# IO.net
KiCad netlist of a schematic drawn in Altium Designer
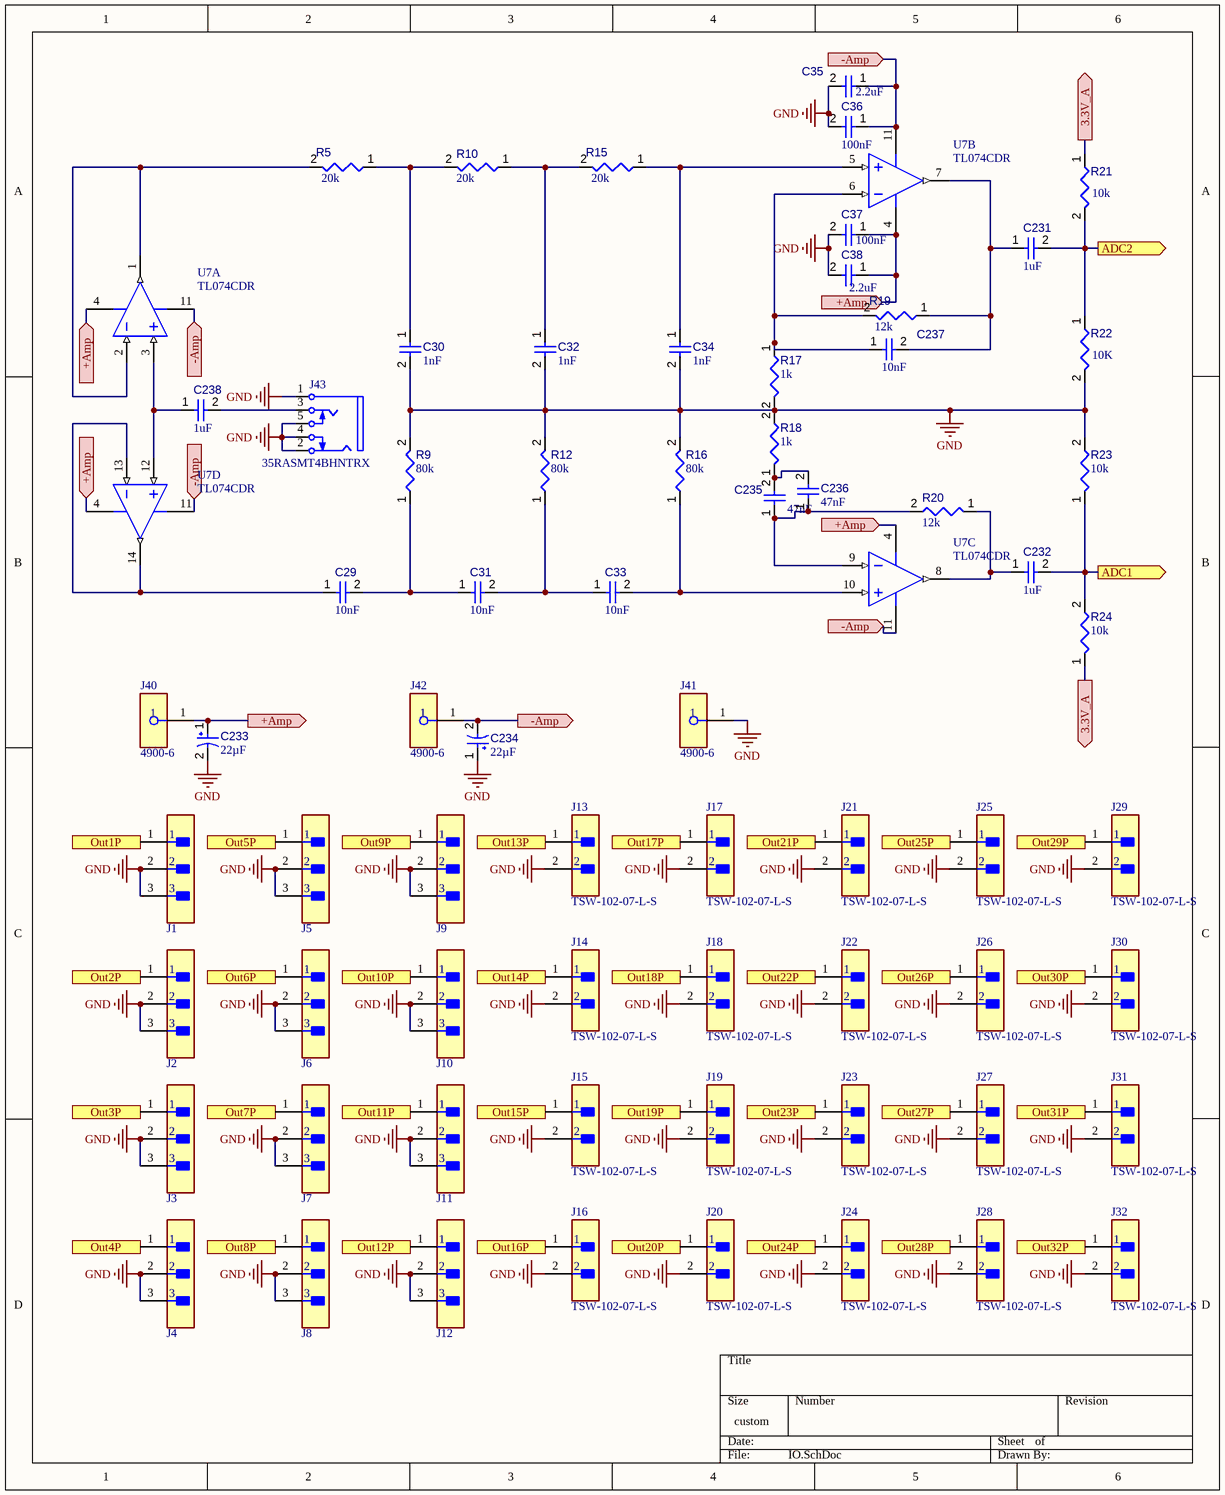
[diagram p0: IO.SchDoc]

(export (version "E")
  (design (tool "Eeschema 10.0.6"))
  (components
    (comp (ref "C29")
      (value "10nF")
      (footprint "CAPC0603(1608)100_L")
      (description "8nF Cap 0603")
      (fields (field (name "TOLERANCE") "10%") (field (name "Comment") "Capacitor 8nF 0603, 12V"))
      (libsource (lib "Northeastern University") (part "CAP-NP-2"))
    )
    (comp (ref "C30")
      (value "1nF")
      (footprint "CAPC0603(1608)100_L")
      (description "1nF 0603")
      (fields (field (name "TOLERANCE") "10%") (field (name "Comment") "Capacitor 1nF 0603, 12V"))
      (libsource (lib "Northeastern University") (part "CAP-NP-2"))
    )
    (comp (ref "C31")
      (value "10nF")
      (footprint "CAPC0603(1608)100_L")
      (description "8nF Cap 0603")
      (fields (field (name "TOLERANCE") "10%") (field (name "Comment") "Capacitor 8nF 0603, 12V"))
      (libsource (lib "Northeastern University") (part "CAP-NP-2"))
    )
    (comp (ref "C32")
      (value "1nF")
      (footprint "CAPC0603(1608)100_L")
      (description "1nF 0603")
      (fields (field (name "TOLERANCE") "10%") (field (name "Comment") "Capacitor 1nF 0603, 12V"))
      (libsource (lib "Northeastern University") (part "CAP-NP-2"))
    )
    (comp (ref "C33")
      (value "10nF")
      (footprint "CAPC0603(1608)100_L")
      (description "8nF Cap 0603")
      (fields (field (name "TOLERANCE") "10%") (field (name "Comment") "Capacitor 10nF 0603, 12V"))
      (libsource (lib "Northeastern University") (part "CAP-NP-2"))
    )
    (comp (ref "C34")
      (value "1nF")
      (footprint "CAPC0603(1608)100_L")
      (description "1nF 0603")
      (fields (field (name "TOLERANCE") "10%") (field (name "Comment") "Capacitor 1nF 0603, 12V"))
      (libsource (lib "Northeastern University") (part "CAP-NP-2"))
    )
    (comp (ref "C35")
      (value "2.2uF")
      (footprint "CAPC0603(1608)100_L")
      (fields (field (name "TOLERANCE") "10%") (field (name "Comment") "Capacitor 2.2uF 0603"))
      (libsource (lib "Northeastern University") (part "CAP-NP-2"))
    )
    (comp (ref "C36")
      (value "100nF")
      (footprint "CAPC0603(1608)100_L")
      (fields (field (name "TOLERANCE") "10%") (field (name "Comment") "Capacitor 100nF 0603"))
      (libsource (lib "Northeastern University") (part "CAP-NP-2"))
    )
    (comp (ref "C37")
      (value "100nF")
      (footprint "CAPC0603(1608)100_L")
      (fields (field (name "TOLERANCE") "10%") (field (name "Comment") "Capacitor 100nF 0603"))
      (libsource (lib "Northeastern University") (part "CAP-NP-2"))
    )
    (comp (ref "C38")
      (value "2.2uF")
      (footprint "CAPC0603(1608)100_L")
      (fields (field (name "TOLERANCE") "10%") (field (name "Comment") "Capacitor 2.2uF 0603"))
      (libsource (lib "Northeastern University") (part "CAP-NP-2"))
    )
    (comp (ref "C231")
      (value "1uF")
      (footprint "CAPC0603(1608)100_L")
      (description "1uF 0603")
      (fields (field (name "TOLERANCE") "10%") (field (name "Comment") "Capacitor 1uF 0603, 12V"))
      (libsource (lib "Northeastern University") (part "CAP-NP-2"))
    )
    (comp (ref "C232")
      (value "1uF")
      (footprint "CAPC0603(1608)100_L")
      (description "1uF 0603")
      (fields (field (name "TOLERANCE") "10%") (field (name "Comment") "Capacitor 1uF 0603, 12V"))
      (libsource (lib "Northeastern University") (part "CAP-NP-2"))
    )
    (comp (ref "C233")
      (value "22µF")
      (footprint "CAPPR55-250-1120X630X1220")
      (description "Aluminum Electrolytic Capacitor, 22 uF, +/- 20%, 100 V, -40 to 85 degC, 2-Pin THD, RoHS, Bulk")
      (fields (field (name "MANUFACTURER") "Panasonic") (field (name "TOLERANCE") "20%"))
      (libsource (lib "Northeastern University") (part "CAP-P-2"))
    )
    (comp (ref "C234")
      (value "22µF")
      (footprint "CAPPR55-250-1120X630X1220")
      (description "Aluminum Electrolytic Capacitor, 22 uF, +/- 20%, 100 V, -40 to 85 degC, 2-Pin THD, RoHS, Bulk")
      (fields (field (name "MANUFACTURER") "Panasonic") (field (name "TOLERANCE") "20%"))
      (libsource (lib "") (part "CAP-P-2_1"))
    )
    (comp (ref "C235")
      (value "47nF")
      (footprint "CAPC0603(1608)100_L")
      (fields (field (name "TOLERANCE") "10%") (field (name "Comment") "Capacitor 47nF 0603"))
      (libsource (lib "Northeastern University") (part "CAP-NP-2"))
    )
    (comp (ref "C236")
      (value "47nF")
      (footprint "CAPC0603(1608)100_L")
      (fields (field (name "TOLERANCE") "10%") (field (name "Comment") "Capacitor 47nF 0603"))
      (libsource (lib "Northeastern University") (part "CAP-NP-2"))
    )
    (comp (ref "C237")
      (value "10nF")
      (footprint "CAPC0603(1608)100_L")
      (description "8nF Cap 0603")
      (fields (field (name "TOLERANCE") "10%") (field (name "Comment") "Capacitor 10nF 0603, 12V"))
      (libsource (lib "Northeastern University") (part "CAP-NP-2"))
    )
    (comp (ref "C238")
      (value "1uF")
      (footprint "CAPC0603(1608)100_L")
      (description "1uF 0603")
      (fields (field (name "TOLERANCE") "10%") (field (name "Comment") "Capacitor 1uF 0603, 12V"))
      (libsource (lib "Northeastern University") (part "CAP-NP-2"))
    )
    (comp (ref "J1")
      (value "87224-3")
      (footprint "FP-87224-3-MFG")
      (description "CONN HEADER VERT 3POS 2.54MM")
      (libsource (lib "Altium Content Vault") (part "0d3f023dd272f625e17a2be33dea85f"))
    )
    (comp (ref "J2")
      (value "87224-3")
      (footprint "FP-87224-3-MFG")
      (description "CONN HEADER VERT 3POS 2.54MM")
      (libsource (lib "Altium Content Vault") (part "0d3f023dd272f625e17a2be33dea85f"))
    )
    (comp (ref "J3")
      (value "87224-3")
      (footprint "FP-87224-3-MFG")
      (description "CONN HEADER VERT 3POS 2.54MM")
      (libsource (lib "Altium Content Vault") (part "0d3f023dd272f625e17a2be33dea85f"))
    )
    (comp (ref "J4")
      (value "87224-3")
      (footprint "FP-87224-3-MFG")
      (description "CONN HEADER VERT 3POS 2.54MM")
      (libsource (lib "Altium Content Vault") (part "0d3f023dd272f625e17a2be33dea85f"))
    )
    (comp (ref "J5")
      (value "87224-3")
      (footprint "FP-87224-3-MFG")
      (description "CONN HEADER VERT 3POS 2.54MM")
      (libsource (lib "Altium Content Vault") (part "0d3f023dd272f625e17a2be33dea85f"))
    )
    (comp (ref "J6")
      (value "87224-3")
      (footprint "FP-87224-3-MFG")
      (description "CONN HEADER VERT 3POS 2.54MM")
      (libsource (lib "Altium Content Vault") (part "0d3f023dd272f625e17a2be33dea85f"))
    )
    (comp (ref "J7")
      (value "87224-3")
      (footprint "FP-87224-3-MFG")
      (description "CONN HEADER VERT 3POS 2.54MM")
      (libsource (lib "Altium Content Vault") (part "0d3f023dd272f625e17a2be33dea85f"))
    )
    (comp (ref "J8")
      (value "87224-3")
      (footprint "FP-87224-3-MFG")
      (description "CONN HEADER VERT 3POS 2.54MM")
      (libsource (lib "Altium Content Vault") (part "0d3f023dd272f625e17a2be33dea85f"))
    )
    (comp (ref "J9")
      (value "87224-3")
      (footprint "FP-87224-3-MFG")
      (description "CONN HEADER VERT 3POS 2.54MM")
      (libsource (lib "Altium Content Vault") (part "0d3f023dd272f625e17a2be33dea85f"))
    )
    (comp (ref "J10")
      (value "87224-3")
      (footprint "FP-87224-3-MFG")
      (description "CONN HEADER VERT 3POS 2.54MM")
      (libsource (lib "Altium Content Vault") (part "0d3f023dd272f625e17a2be33dea85f"))
    )
    (comp (ref "J11")
      (value "87224-3")
      (footprint "FP-87224-3-MFG")
      (description "CONN HEADER VERT 3POS 2.54MM")
      (libsource (lib "Altium Content Vault") (part "0d3f023dd272f625e17a2be33dea85f"))
    )
    (comp (ref "J12")
      (value "87224-3")
      (footprint "FP-87224-3-MFG")
      (description "CONN HEADER VERT 3POS 2.54MM")
      (libsource (lib "Altium Content Vault") (part "0d3f023dd272f625e17a2be33dea85f"))
    )
    (comp (ref "J13")
      (value "TSW-102-07-L-S")
      (footprint "FP-TSW-102-07-L-S-MFG")
      (description "CONN HEADER VERT 2POS 2.54MM")
      (libsource (lib "Altium Content Vault") (part "3bc925449376181038e59eaffc5286c"))
    )
    (comp (ref "J14")
      (value "TSW-102-07-L-S")
      (footprint "FP-TSW-102-07-L-S-MFG")
      (description "CONN HEADER VERT 2POS 2.54MM")
      (libsource (lib "Altium Content Vault") (part "3bc925449376181038e59eaffc5286c"))
    )
    (comp (ref "J15")
      (value "TSW-102-07-L-S")
      (footprint "FP-TSW-102-07-L-S-MFG")
      (description "CONN HEADER VERT 2POS 2.54MM")
      (libsource (lib "Altium Content Vault") (part "3bc925449376181038e59eaffc5286c"))
    )
    (comp (ref "J16")
      (value "TSW-102-07-L-S")
      (footprint "FP-TSW-102-07-L-S-MFG")
      (description "CONN HEADER VERT 2POS 2.54MM")
      (libsource (lib "Altium Content Vault") (part "3bc925449376181038e59eaffc5286c"))
    )
    (comp (ref "J17")
      (value "TSW-102-07-L-S")
      (footprint "FP-TSW-102-07-L-S-MFG")
      (description "CONN HEADER VERT 2POS 2.54MM")
      (libsource (lib "Altium Content Vault") (part "3bc925449376181038e59eaffc5286c"))
    )
    (comp (ref "J18")
      (value "TSW-102-07-L-S")
      (footprint "FP-TSW-102-07-L-S-MFG")
      (description "CONN HEADER VERT 2POS 2.54MM")
      (libsource (lib "Altium Content Vault") (part "3bc925449376181038e59eaffc5286c"))
    )
    (comp (ref "J19")
      (value "TSW-102-07-L-S")
      (footprint "FP-TSW-102-07-L-S-MFG")
      (description "CONN HEADER VERT 2POS 2.54MM")
      (libsource (lib "Altium Content Vault") (part "3bc925449376181038e59eaffc5286c"))
    )
    (comp (ref "J20")
      (value "TSW-102-07-L-S")
      (footprint "FP-TSW-102-07-L-S-MFG")
      (description "CONN HEADER VERT 2POS 2.54MM")
      (libsource (lib "Altium Content Vault") (part "3bc925449376181038e59eaffc5286c"))
    )
    (comp (ref "J21")
      (value "TSW-102-07-L-S")
      (footprint "FP-TSW-102-07-L-S-MFG")
      (description "CONN HEADER VERT 2POS 2.54MM")
      (libsource (lib "Altium Content Vault") (part "3bc925449376181038e59eaffc5286c"))
    )
    (comp (ref "J22")
      (value "TSW-102-07-L-S")
      (footprint "FP-TSW-102-07-L-S-MFG")
      (description "CONN HEADER VERT 2POS 2.54MM")
      (libsource (lib "Altium Content Vault") (part "3bc925449376181038e59eaffc5286c"))
    )
    (comp (ref "J23")
      (value "TSW-102-07-L-S")
      (footprint "FP-TSW-102-07-L-S-MFG")
      (description "CONN HEADER VERT 2POS 2.54MM")
      (libsource (lib "Altium Content Vault") (part "3bc925449376181038e59eaffc5286c"))
    )
    (comp (ref "J24")
      (value "TSW-102-07-L-S")
      (footprint "FP-TSW-102-07-L-S-MFG")
      (description "CONN HEADER VERT 2POS 2.54MM")
      (libsource (lib "Altium Content Vault") (part "3bc925449376181038e59eaffc5286c"))
    )
    (comp (ref "J25")
      (value "TSW-102-07-L-S")
      (footprint "FP-TSW-102-07-L-S-MFG")
      (description "CONN HEADER VERT 2POS 2.54MM")
      (libsource (lib "Altium Content Vault") (part "3bc925449376181038e59eaffc5286c"))
    )
    (comp (ref "J26")
      (value "TSW-102-07-L-S")
      (footprint "FP-TSW-102-07-L-S-MFG")
      (description "CONN HEADER VERT 2POS 2.54MM")
      (libsource (lib "Altium Content Vault") (part "3bc925449376181038e59eaffc5286c"))
    )
    (comp (ref "J27")
      (value "TSW-102-07-L-S")
      (footprint "FP-TSW-102-07-L-S-MFG")
      (description "CONN HEADER VERT 2POS 2.54MM")
      (libsource (lib "Altium Content Vault") (part "3bc925449376181038e59eaffc5286c"))
    )
    (comp (ref "J28")
      (value "TSW-102-07-L-S")
      (footprint "FP-TSW-102-07-L-S-MFG")
      (description "CONN HEADER VERT 2POS 2.54MM")
      (libsource (lib "Altium Content Vault") (part "3bc925449376181038e59eaffc5286c"))
    )
    (comp (ref "J29")
      (value "TSW-102-07-L-S")
      (footprint "FP-TSW-102-07-L-S-MFG")
      (description "CONN HEADER VERT 2POS 2.54MM")
      (libsource (lib "Altium Content Vault") (part "3bc925449376181038e59eaffc5286c"))
    )
    (comp (ref "J30")
      (value "TSW-102-07-L-S")
      (footprint "FP-TSW-102-07-L-S-MFG")
      (description "CONN HEADER VERT 2POS 2.54MM")
      (libsource (lib "Altium Content Vault") (part "3bc925449376181038e59eaffc5286c"))
    )
    (comp (ref "J31")
      (value "TSW-102-07-L-S")
      (footprint "FP-TSW-102-07-L-S-MFG")
      (description "CONN HEADER VERT 2POS 2.54MM")
      (libsource (lib "Altium Content Vault") (part "3bc925449376181038e59eaffc5286c"))
    )
    (comp (ref "J32")
      (value "TSW-102-07-L-S")
      (footprint "FP-TSW-102-07-L-S-MFG")
      (description "CONN HEADER VERT 2POS 2.54MM")
      (libsource (lib "Altium Content Vault") (part "3bc925449376181038e59eaffc5286c"))
    )
    (comp (ref "J40")
      (value "4900-6")
      (footprint "FP-4900-6-MFG")
      (description "CONN BANANA JACK TURRET BLUE")
      (libsource (lib "Altium Content Vault") (part "c5c826e0c4b67fe3b42ef77f2d4decc"))
    )
    (comp (ref "J41")
      (value "4900-6")
      (footprint "FP-4900-6-MFG")
      (description "CONN BANANA JACK TURRET BLUE")
      (libsource (lib "Altium Content Vault") (part "c5c826e0c4b67fe3b42ef77f2d4decc"))
    )
    (comp (ref "J42")
      (value "4900-6")
      (footprint "FP-4900-6-MFG")
      (description "CONN BANANA JACK TURRET BLUE")
      (libsource (lib "Altium Content Vault") (part "c5c826e0c4b67fe3b42ef77f2d4decc"))
    )
    (comp (ref "J43")
      (value "35RASMT4BHNTRX")
      (footprint "SWIT-35RASMT4BHNTRX_V")
      (description "Female 3.5 mm Phone Jack, 5 Position, Height 5 mm, RoHS, Tape and Reel")
      (fields (field (name "MANUFACTURER") "Switchcraft"))
      (libsource (lib "Northeastern University") (part "JACK-3CD5-RN"))
    )
    (comp (ref "R5")
      (value "20k")
      (footprint "RESC0603(1608)_L")
      (description "20k 0603")
      (fields (field (name "Comment") "Resistor 20k 0603, 12V"))
      (libsource (lib "Northeastern University") (part "RES-2"))
    )
    (comp (ref "R9")
      (value "80k")
      (footprint "RESC0603(1608)_L")
      (description "80k 0603")
      (fields (field (name "Comment") "Resistor 80k 0603, 12V"))
      (libsource (lib "Northeastern University") (part "RES-2"))
    )
    (comp (ref "R10")
      (value "20k")
      (footprint "RESC0603(1608)_L")
      (description "20k 0603")
      (fields (field (name "Comment") "Resistor 20k 0603, 12V"))
      (libsource (lib "Northeastern University") (part "RES-2"))
    )
    (comp (ref "R12")
      (value "80k")
      (footprint "RESC0603(1608)_L")
      (description "80k 0603")
      (fields (field (name "Comment") "Resistor 80k 0603, 12V"))
      (libsource (lib "Northeastern University") (part "RES-2"))
    )
    (comp (ref "R15")
      (value "20k")
      (footprint "RESC0603(1608)_L")
      (description "20k 0603")
      (fields (field (name "Comment") "Resistor 20k 0603, 12V"))
      (libsource (lib "Northeastern University") (part "RES-2"))
    )
    (comp (ref "R16")
      (value "80k")
      (footprint "RESC0603(1608)_L")
      (description "80k 0603")
      (fields (field (name "Comment") "Resistor 80k 0603, 12V"))
      (libsource (lib "Northeastern University") (part "RES-2"))
    )
    (comp (ref "R17")
      (value "1k")
      (footprint "RESC0603(1608)_L")
      (description "1k 0603")
      (fields (field (name "Comment") "Resistor 1k 0603, 12V"))
      (libsource (lib "Northeastern University") (part "RES-2"))
    )
    (comp (ref "R18")
      (value "1k")
      (footprint "RESC0603(1608)_L")
      (description "1k 0603")
      (fields (field (name "Comment") "Resistor 1k 0603, 12V"))
      (libsource (lib "Northeastern University") (part "RES-2"))
    )
    (comp (ref "R19")
      (value "12k")
      (footprint "RESC0603(1608)_L")
      (description "12k 0603")
      (fields (field (name "Comment") "Resistor 12k 0603, 12V"))
      (libsource (lib "Northeastern University") (part "RES-2"))
    )
    (comp (ref "R20")
      (value "12k")
      (footprint "RESC0603(1608)_L")
      (description "12k 0603")
      (fields (field (name "Comment") "Resistor 12k 0603, 12V"))
      (libsource (lib "Northeastern University") (part "RES-2"))
    )
    (comp (ref "R21")
      (value "10k")
      (footprint "RESC0603(1608)_L")
      (description "10k 0603")
      (fields (field (name "Comment") "Resistor 10k 0603, 12V"))
      (libsource (lib "Northeastern University") (part "RES-2"))
    )
    (comp (ref "R22")
      (value "10K")
      (footprint "RESC0603(1608)_L")
      (description "10k 0603")
      (fields (field (name "Comment") "Resistor 10k 0603, 12V"))
      (libsource (lib "Northeastern University") (part "RES-2"))
    )
    (comp (ref "R23")
      (value "10k")
      (footprint "RESC0603(1608)_L")
      (description "10k 0603")
      (fields (field (name "Comment") "Resistor 10k 0603, 12V"))
      (libsource (lib "Northeastern University") (part "RES-2"))
    )
    (comp (ref "R24")
      (value "10k")
      (footprint "RESC0603(1608)_L")
      (description "10k 0603")
      (fields (field (name "Comment") "Resistor 10k 0603, 12V"))
      (libsource (lib "Northeastern University") (part "RES-2"))
    )
    (comp (ref "U7")
      (value "TL074CDR")
      (footprint "D0014A_N")
      (fields (field (name "MANUFACTURER") "Texas Instruments"))
      (libsource (lib "Altium Content Vault") (part "TI-TLXX4X_MC3403-X14"))
    )
  )
  (nets
    (net (code "1") (name "/+Amp") (class "Default")
      (node (ref "C233") (pin "1") (pinfunction "1_1") (pintype "passive"))
      (node (ref "C37") (pin "1") (pinfunction "1_1") (pintype "passive"))
      (node (ref "C38") (pin "1") (pinfunction "1_1") (pintype "passive"))
      (node (ref "J40") (pin "1") (pinfunction "1_1") (pintype "passive"))
      (node (ref "U7") (pin "4") (pinfunction "VCC+_4") (pintype "power_in"))
    )
    (net (code "2") (name "/-Amp") (class "Default")
      (node (ref "C234") (pin "2") (pinfunction "2_2") (pintype "passive"))
      (node (ref "C35") (pin "1") (pinfunction "1_1") (pintype "passive"))
      (node (ref "C36") (pin "1") (pinfunction "1_1") (pintype "passive"))
      (node (ref "J42") (pin "1") (pinfunction "1_1") (pintype "passive"))
      (node (ref "U7") (pin "11") (pinfunction "VCC-_11") (pintype "power_in"))
    )
    (net (code "3") (name "/3.3V_A") (class "Default")
      (node (ref "R21") (pin "1") (pinfunction "1_1") (pintype "passive"))
      (node (ref "R24") (pin "1") (pinfunction "1_1") (pintype "passive"))
    )
    (net (code "4") (name "/ADC1") (class "Default")
      (node (ref "C232") (pin "2") (pinfunction "2_2") (pintype "passive"))
      (node (ref "R23") (pin "1") (pinfunction "1_1") (pintype "passive"))
      (node (ref "R24") (pin "2") (pinfunction "2_2") (pintype "passive"))
    )
    (net (code "5") (name "/ADC2") (class "Default")
      (node (ref "C231") (pin "2") (pinfunction "2_2") (pintype "passive"))
      (node (ref "R21") (pin "2") (pinfunction "2_2") (pintype "passive"))
      (node (ref "R22") (pin "1") (pinfunction "1_1") (pintype "passive"))
    )
    (net (code "6") (name "/Out1P") (class "Default")
      (node (ref "J1") (pin "1") (pinfunction "1_1") (pintype "passive"))
    )
    (net (code "7") (name "/Out2P") (class "Default")
      (node (ref "J2") (pin "1") (pinfunction "1_1") (pintype "passive"))
    )
    (net (code "8") (name "/Out3P") (class "Default")
      (node (ref "J3") (pin "1") (pinfunction "1_1") (pintype "passive"))
    )
    (net (code "9") (name "/Out4P") (class "Default")
      (node (ref "J4") (pin "1") (pinfunction "1_1") (pintype "passive"))
    )
    (net (code "10") (name "/Out5P") (class "Default")
      (node (ref "J5") (pin "1") (pinfunction "1_1") (pintype "passive"))
    )
    (net (code "11") (name "/Out6P") (class "Default")
      (node (ref "J6") (pin "1") (pinfunction "1_1") (pintype "passive"))
    )
    (net (code "12") (name "/Out7P") (class "Default")
      (node (ref "J7") (pin "1") (pinfunction "1_1") (pintype "passive"))
    )
    (net (code "13") (name "/Out8P") (class "Default")
      (node (ref "J8") (pin "1") (pinfunction "1_1") (pintype "passive"))
    )
    (net (code "14") (name "/Out9P") (class "Default")
      (node (ref "J9") (pin "1") (pinfunction "1_1") (pintype "passive"))
    )
    (net (code "15") (name "/Out10P") (class "Default")
      (node (ref "J10") (pin "1") (pinfunction "1_1") (pintype "passive"))
    )
    (net (code "16") (name "/Out11P") (class "Default")
      (node (ref "J11") (pin "1") (pinfunction "1_1") (pintype "passive"))
    )
    (net (code "17") (name "/Out12P") (class "Default")
      (node (ref "J12") (pin "1") (pinfunction "1_1") (pintype "passive"))
    )
    (net (code "18") (name "/Out13P") (class "Default")
      (node (ref "J13") (pin "1") (pinfunction "1_1") (pintype "passive"))
    )
    (net (code "19") (name "/Out14P") (class "Default")
      (node (ref "J14") (pin "1") (pinfunction "1_1") (pintype "passive"))
    )
    (net (code "20") (name "/Out15P") (class "Default")
      (node (ref "J15") (pin "1") (pinfunction "1_1") (pintype "passive"))
    )
    (net (code "21") (name "/Out16P") (class "Default")
      (node (ref "J16") (pin "1") (pinfunction "1_1") (pintype "passive"))
    )
    (net (code "22") (name "/Out17P") (class "Default")
      (node (ref "J17") (pin "1") (pinfunction "1_1") (pintype "passive"))
    )
    (net (code "23") (name "/Out18P") (class "Default")
      (node (ref "J18") (pin "1") (pinfunction "1_1") (pintype "passive"))
    )
    (net (code "24") (name "/Out19P") (class "Default")
      (node (ref "J19") (pin "1") (pinfunction "1_1") (pintype "passive"))
    )
    (net (code "25") (name "/Out20P") (class "Default")
      (node (ref "J20") (pin "1") (pinfunction "1_1") (pintype "passive"))
    )
    (net (code "26") (name "/Out21P") (class "Default")
      (node (ref "J21") (pin "1") (pinfunction "1_1") (pintype "passive"))
    )
    (net (code "27") (name "/Out22P") (class "Default")
      (node (ref "J22") (pin "1") (pinfunction "1_1") (pintype "passive"))
    )
    (net (code "28") (name "/Out23P") (class "Default")
      (node (ref "J23") (pin "1") (pinfunction "1_1") (pintype "passive"))
    )
    (net (code "29") (name "/Out24P") (class "Default")
      (node (ref "J24") (pin "1") (pinfunction "1_1") (pintype "passive"))
    )
    (net (code "30") (name "/Out25P") (class "Default")
      (node (ref "J25") (pin "1") (pinfunction "1_1") (pintype "passive"))
    )
    (net (code "31") (name "/Out26P") (class "Default")
      (node (ref "J26") (pin "1") (pinfunction "1_1") (pintype "passive"))
    )
    (net (code "32") (name "/Out27P") (class "Default")
      (node (ref "J27") (pin "1") (pinfunction "1_1") (pintype "passive"))
    )
    (net (code "33") (name "/Out28P") (class "Default")
      (node (ref "J28") (pin "1") (pinfunction "1_1") (pintype "passive"))
    )
    (net (code "34") (name "/Out29P") (class "Default")
      (node (ref "J29") (pin "1") (pinfunction "1_1") (pintype "passive"))
    )
    (net (code "35") (name "/Out30P") (class "Default")
      (node (ref "J30") (pin "1") (pinfunction "1_1") (pintype "passive"))
    )
    (net (code "36") (name "/Out31P") (class "Default")
      (node (ref "J31") (pin "1") (pinfunction "1_1") (pintype "passive"))
    )
    (net (code "37") (name "/Out32P") (class "Default")
      (node (ref "J32") (pin "1") (pinfunction "1_1") (pintype "passive"))
    )
    (net (code "38") (name "GND") (class "Default")
      (node (ref "C233") (pin "2") (pinfunction "2_2") (pintype "passive"))
      (node (ref "C234") (pin "1") (pinfunction "1_1") (pintype "passive"))
      (node (ref "C30") (pin "2") (pinfunction "2_2") (pintype "passive"))
      (node (ref "C32") (pin "2") (pinfunction "2_2") (pintype "passive"))
      (node (ref "C34") (pin "2") (pinfunction "2_2") (pintype "passive"))
      (node (ref "C35") (pin "2") (pinfunction "2_2") (pintype "passive"))
      (node (ref "C36") (pin "2") (pinfunction "2_2") (pintype "passive"))
      (node (ref "C37") (pin "2") (pinfunction "2_2") (pintype "passive"))
      (node (ref "C38") (pin "2") (pinfunction "2_2") (pintype "passive"))
      (node (ref "J1") (pin "2") (pinfunction "2_2") (pintype "passive"))
      (node (ref "J1") (pin "3") (pinfunction "3_3") (pintype "passive"))
      (node (ref "J10") (pin "2") (pinfunction "2_2") (pintype "passive"))
      (node (ref "J10") (pin "3") (pinfunction "3_3") (pintype "passive"))
      (node (ref "J11") (pin "2") (pinfunction "2_2") (pintype "passive"))
      (node (ref "J11") (pin "3") (pinfunction "3_3") (pintype "passive"))
      (node (ref "J12") (pin "2") (pinfunction "2_2") (pintype "passive"))
      (node (ref "J12") (pin "3") (pinfunction "3_3") (pintype "passive"))
      (node (ref "J13") (pin "2") (pinfunction "2_2") (pintype "passive"))
      (node (ref "J14") (pin "2") (pinfunction "2_2") (pintype "passive"))
      (node (ref "J15") (pin "2") (pinfunction "2_2") (pintype "passive"))
      (node (ref "J16") (pin "2") (pinfunction "2_2") (pintype "passive"))
      (node (ref "J17") (pin "2") (pinfunction "2_2") (pintype "passive"))
      (node (ref "J18") (pin "2") (pinfunction "2_2") (pintype "passive"))
      (node (ref "J19") (pin "2") (pinfunction "2_2") (pintype "passive"))
      (node (ref "J2") (pin "2") (pinfunction "2_2") (pintype "passive"))
      (node (ref "J2") (pin "3") (pinfunction "3_3") (pintype "passive"))
      (node (ref "J20") (pin "2") (pinfunction "2_2") (pintype "passive"))
      (node (ref "J21") (pin "2") (pinfunction "2_2") (pintype "passive"))
      (node (ref "J22") (pin "2") (pinfunction "2_2") (pintype "passive"))
      (node (ref "J23") (pin "2") (pinfunction "2_2") (pintype "passive"))
      (node (ref "J24") (pin "2") (pinfunction "2_2") (pintype "passive"))
      (node (ref "J25") (pin "2") (pinfunction "2_2") (pintype "passive"))
      (node (ref "J26") (pin "2") (pinfunction "2_2") (pintype "passive"))
      (node (ref "J27") (pin "2") (pinfunction "2_2") (pintype "passive"))
      (node (ref "J28") (pin "2") (pinfunction "2_2") (pintype "passive"))
      (node (ref "J29") (pin "2") (pinfunction "2_2") (pintype "passive"))
      (node (ref "J3") (pin "2") (pinfunction "2_2") (pintype "passive"))
      (node (ref "J3") (pin "3") (pinfunction "3_3") (pintype "passive"))
      (node (ref "J30") (pin "2") (pinfunction "2_2") (pintype "passive"))
      (node (ref "J31") (pin "2") (pinfunction "2_2") (pintype "passive"))
      (node (ref "J32") (pin "2") (pinfunction "2_2") (pintype "passive"))
      (node (ref "J4") (pin "2") (pinfunction "2_2") (pintype "passive"))
      (node (ref "J4") (pin "3") (pinfunction "3_3") (pintype "passive"))
      (node (ref "J41") (pin "1") (pinfunction "1_1") (pintype "passive"))
      (node (ref "J43") (pin "1") (pinfunction "1_1") (pintype "passive"))
      (node (ref "J43") (pin "2") (pinfunction "2_2") (pintype "passive"))
      (node (ref "J43") (pin "4") (pinfunction "4_4") (pintype "passive"))
      (node (ref "J43") (pin "5") (pinfunction "5_5") (pintype "passive"))
      (node (ref "J5") (pin "2") (pinfunction "2_2") (pintype "passive"))
      (node (ref "J5") (pin "3") (pinfunction "3_3") (pintype "passive"))
      (node (ref "J6") (pin "2") (pinfunction "2_2") (pintype "passive"))
      (node (ref "J6") (pin "3") (pinfunction "3_3") (pintype "passive"))
      (node (ref "J7") (pin "2") (pinfunction "2_2") (pintype "passive"))
      (node (ref "J7") (pin "3") (pinfunction "3_3") (pintype "passive"))
      (node (ref "J8") (pin "2") (pinfunction "2_2") (pintype "passive"))
      (node (ref "J8") (pin "3") (pinfunction "3_3") (pintype "passive"))
      (node (ref "J9") (pin "2") (pinfunction "2_2") (pintype "passive"))
      (node (ref "J9") (pin "3") (pinfunction "3_3") (pintype "passive"))
      (node (ref "R12") (pin "2") (pinfunction "2_2") (pintype "passive"))
      (node (ref "R16") (pin "2") (pinfunction "2_2") (pintype "passive"))
      (node (ref "R17") (pin "2") (pinfunction "2_2") (pintype "passive"))
      (node (ref "R18") (pin "2") (pinfunction "2_2") (pintype "passive"))
      (node (ref "R22") (pin "2") (pinfunction "2_2") (pintype "passive"))
      (node (ref "R23") (pin "2") (pinfunction "2_2") (pintype "passive"))
      (node (ref "R9") (pin "2") (pinfunction "2_2") (pintype "passive"))
    )
    (net (code "39") (name "Net-(C29-Pad2)") (class "Default")
      (node (ref "C29") (pin "2") (pinfunction "2_2") (pintype "passive"))
      (node (ref "C31") (pin "1") (pinfunction "1_1") (pintype "passive"))
      (node (ref "R9") (pin "1") (pinfunction "1_1") (pintype "passive"))
    )
    (net (code "40") (name "Net-(C30-Pad1)") (class "Default")
      (node (ref "C30") (pin "1") (pinfunction "1_1") (pintype "passive"))
      (node (ref "R10") (pin "2") (pinfunction "2_2") (pintype "passive"))
      (node (ref "R5") (pin "1") (pinfunction "1_1") (pintype "passive"))
    )
    (net (code "41") (name "Net-(C31-Pad2)") (class "Default")
      (node (ref "C31") (pin "2") (pinfunction "2_2") (pintype "passive"))
      (node (ref "C33") (pin "1") (pinfunction "1_1") (pintype "passive"))
      (node (ref "R12") (pin "1") (pinfunction "1_1") (pintype "passive"))
    )
    (net (code "42") (name "Net-(C32-Pad1)") (class "Default")
      (node (ref "C32") (pin "1") (pinfunction "1_1") (pintype "passive"))
      (node (ref "R10") (pin "1") (pinfunction "1_1") (pintype "passive"))
      (node (ref "R15") (pin "2") (pinfunction "2_2") (pintype "passive"))
    )
    (net (code "43") (name "Net-(C235-Pad2)") (class "Default")
      (node (ref "C235") (pin "2") (pinfunction "2_2") (pintype "passive"))
      (node (ref "C236") (pin "2") (pinfunction "2_2") (pintype "passive"))
      (node (ref "R18") (pin "1") (pinfunction "1_1") (pintype "passive"))
    )
    (net (code "44") (name "Net-(C238-Pad2)") (class "Default")
      (node (ref "C238") (pin "2") (pinfunction "2_2") (pintype "passive"))
      (node (ref "J43") (pin "3") (pinfunction "3_3") (pintype "passive"))
    )
    (net (code "45") (name "Net-(U7A-IN1+)") (class "Default")
      (node (ref "C238") (pin "1") (pinfunction "1_1") (pintype "passive"))
      (node (ref "U7") (pin "12") (pinfunction "IN4+_12") (pintype "input"))
      (node (ref "U7") (pin "3") (pinfunction "IN1+_3") (pintype "input"))
    )
    (net (code "46") (name "Net-(U7A-IN1-)") (class "Default")
      (node (ref "R5") (pin "2") (pinfunction "2_2") (pintype "passive"))
      (node (ref "U7") (pin "1") (pinfunction "OUT1_1") (pintype "output"))
      (node (ref "U7") (pin "2") (pinfunction "IN1-_2") (pintype "input"))
    )
    (net (code "47") (name "Net-(U7B-IN2+)") (class "Default")
      (node (ref "C34") (pin "1") (pinfunction "1_1") (pintype "passive"))
      (node (ref "R15") (pin "1") (pinfunction "1_1") (pintype "passive"))
      (node (ref "U7") (pin "5") (pinfunction "IN2+_5") (pintype "input"))
    )
    (net (code "48") (name "Net-(U7B-IN2-)") (class "Default")
      (node (ref "C237") (pin "1") (pinfunction "1_1") (pintype "passive"))
      (node (ref "R17") (pin "1") (pinfunction "1_1") (pintype "passive"))
      (node (ref "R19") (pin "2") (pinfunction "2_2") (pintype "passive"))
      (node (ref "U7") (pin "6") (pinfunction "IN2-_6") (pintype "input"))
    )
    (net (code "49") (name "Net-(U7B-OUT2)") (class "Default")
      (node (ref "C231") (pin "1") (pinfunction "1_1") (pintype "passive"))
      (node (ref "C237") (pin "2") (pinfunction "2_2") (pintype "passive"))
      (node (ref "R19") (pin "1") (pinfunction "1_1") (pintype "passive"))
      (node (ref "U7") (pin "7") (pinfunction "OUT2_7") (pintype "output"))
    )
    (net (code "50") (name "Net-(U7C-IN3+)") (class "Default")
      (node (ref "C33") (pin "2") (pinfunction "2_2") (pintype "passive"))
      (node (ref "R16") (pin "1") (pinfunction "1_1") (pintype "passive"))
      (node (ref "U7") (pin "10") (pinfunction "IN3+_10") (pintype "input"))
    )
    (net (code "51") (name "Net-(U7C-IN3-)") (class "Default")
      (node (ref "C235") (pin "1") (pinfunction "1_1") (pintype "passive"))
      (node (ref "C236") (pin "1") (pinfunction "1_1") (pintype "passive"))
      (node (ref "R20") (pin "2") (pinfunction "2_2") (pintype "passive"))
      (node (ref "U7") (pin "9") (pinfunction "IN3-_9") (pintype "input"))
    )
    (net (code "52") (name "Net-(U7C-OUT3)") (class "Default")
      (node (ref "C232") (pin "1") (pinfunction "1_1") (pintype "passive"))
      (node (ref "R20") (pin "1") (pinfunction "1_1") (pintype "passive"))
      (node (ref "U7") (pin "8") (pinfunction "OUT3_8") (pintype "output"))
    )
    (net (code "53") (name "Net-(U7D-IN4-)") (class "Default")
      (node (ref "C29") (pin "1") (pinfunction "1_1") (pintype "passive"))
      (node (ref "U7") (pin "13") (pinfunction "IN4-_13") (pintype "input"))
      (node (ref "U7") (pin "14") (pinfunction "OUT4_14") (pintype "output"))
    )
  )
)
